# 9xmodule_routed.net
KiCad netlist of a schematic drawn in EAGLE
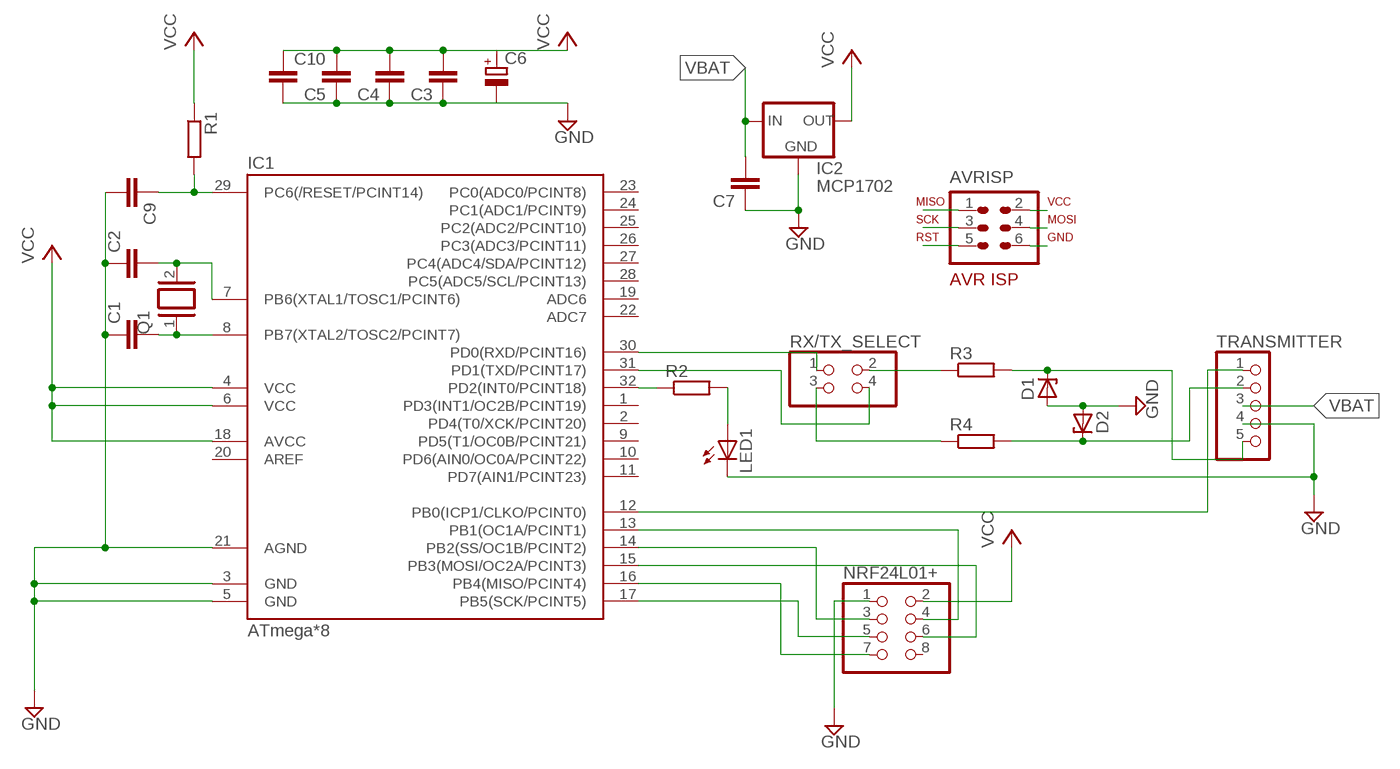
[diagram p0: schematic, sheet 1]

(export (version "E")
  (design (tool "Eeschema 10.0.6"))
  (components
    (comp (ref "AVRISP")
      (value "AVR-ISP-6VERT")
      (footprint "eagle-import:AVR-ISP-6")
      (libsource (lib "eagle-import") (part "AVR-ISP-6VERT"))
    )
    (comp (ref "C1")
      (value "C-EUC0805")
      (footprint "eagle-import:C0805")
      (libsource (lib "eagle-import") (part "C-EUC0805"))
    )
    (comp (ref "C2")
      (value "C-EUC0805")
      (footprint "eagle-import:C0805")
      (libsource (lib "eagle-import") (part "C-EUC0805"))
    )
    (comp (ref "C3")
      (value "C-EUC0805")
      (footprint "eagle-import:C0805")
      (libsource (lib "eagle-import") (part "C-EUC0805"))
    )
    (comp (ref "C4")
      (value "C-EUC0805")
      (footprint "eagle-import:C0805")
      (libsource (lib "eagle-import") (part "C-EUC0805"))
    )
    (comp (ref "C5")
      (value "C-EUC0805")
      (footprint "eagle-import:C0805")
      (libsource (lib "eagle-import") (part "C-EUC0805"))
    )
    (comp (ref "C6")
      (value "CPOL-EUE2.5-6")
      (footprint "eagle-import:E2,5-6")
      (libsource (lib "eagle-import") (part "CPOL-EUE2.5-6"))
    )
    (comp (ref "C7")
      (value "C-EUC0805")
      (footprint "eagle-import:C0805")
      (libsource (lib "eagle-import") (part "C-EUC0805"))
    )
    (comp (ref "C9")
      (value "C-EUC0805")
      (footprint "eagle-import:C0805")
      (libsource (lib "eagle-import") (part "C-EUC0805"))
    )
    (comp (ref "C10")
      (value "C-EUC0805")
      (footprint "eagle-import:C0805")
      (libsource (lib "eagle-import") (part "C-EUC0805"))
    )
    (comp (ref "D1")
      (value "ZENER-DIODESOD80C")
      (footprint "eagle-import:SOD80C")
      (libsource (lib "eagle-import") (part "ZENER-DIODESOD80C"))
    )
    (comp (ref "D2")
      (value "ZENER-DIODESOD80C")
      (footprint "eagle-import:SOD80C")
      (libsource (lib "eagle-import") (part "ZENER-DIODESOD80C"))
    )
    (comp (ref "IC1")
      (value "ATmega*8")
      (footprint "eagle-import:TQFP32-08")
      (libsource (lib "eagle-import") (part "MEGA48/88/168-AU"))
    )
    (comp (ref "IC2")
      (value "MCP1702")
      (footprint "eagle-import:TO-92")
      (libsource (lib "eagle-import") (part "MCP1702"))
    )
    (comp (ref "LED1")
      (value "LEDSMT1206")
      (footprint "eagle-import:1206")
      (libsource (lib "eagle-import") (part "LEDSMT1206"))
    )
    (comp (ref "NRF24L01+")
      (value "PINHD-2X4")
      (footprint "eagle-import:2X04")
      (libsource (lib "eagle-import") (part "PINHD-2X4"))
    )
    (comp (ref "Q1")
      (value "XTAL/S")
      (footprint "eagle-import:QS")
      (libsource (lib "eagle-import") (part "XTAL/S"))
    )
    (comp (ref "R1")
      (value "R-EU_M0805")
      (footprint "eagle-import:M0805")
      (libsource (lib "eagle-import") (part "R-EU_M0805"))
    )
    (comp (ref "R2")
      (value "R-EU_M0805")
      (footprint "eagle-import:M0805")
      (libsource (lib "eagle-import") (part "R-EU_M0805"))
    )
    (comp (ref "R3")
      (value "R-EU_M0805")
      (footprint "eagle-import:M0805")
      (libsource (lib "eagle-import") (part "R-EU_M0805"))
    )
    (comp (ref "R4")
      (value "R-EU_M0805")
      (footprint "eagle-import:M0805")
      (libsource (lib "eagle-import") (part "R-EU_M0805"))
    )
    (comp (ref "RX/TX_SELECT")
      (value "PINHD-2X2")
      (footprint "eagle-import:2X02")
      (libsource (lib "eagle-import") (part "PINHD-2X2"))
    )
    (comp (ref "TRANSMITTER")
      (value "PINHD-1X5")
      (footprint "eagle-import:1X05")
      (libsource (lib "eagle-import") (part "PINHD-1X5"))
    )
  )
  (nets
    (net (code "1") (name "/MISO") (class "Default")
      (node (ref "AVRISP") (pin "1") (pinfunction "1_1") (pintype "passive"))
      (node (ref "IC1") (pin "16") (pinfunction "PB4(MISO/PCINT4)_16") (pintype "bidirectional"))
      (node (ref "NRF24L01+") (pin "7") (pinfunction "7_7") (pintype "passive"))
    )
    (net (code "2") (name "/MOSI") (class "Default")
      (node (ref "AVRISP") (pin "4") (pinfunction "4_4") (pintype "passive"))
      (node (ref "IC1") (pin "15") (pinfunction "PB3(MOSI/OC2A/PCINT3)_15") (pintype "bidirectional"))
      (node (ref "NRF24L01+") (pin "6") (pinfunction "6_6") (pintype "passive"))
    )
    (net (code "3") (name "/RST") (class "Default")
      (node (ref "AVRISP") (pin "5") (pinfunction "5_5") (pintype "passive"))
      (node (ref "C9") (pin "1") (pinfunction "1_1") (pintype "passive"))
      (node (ref "IC1") (pin "29") (pinfunction "PC6(/RESET/PCINT14)_29") (pintype "bidirectional"))
      (node (ref "R1") (pin "2") (pinfunction "2_2") (pintype "passive"))
    )
    (net (code "4") (name "/SCK") (class "Default")
      (node (ref "AVRISP") (pin "3") (pinfunction "3_3") (pintype "passive"))
      (node (ref "IC1") (pin "17") (pinfunction "PB5(SCK/PCINT5)_17") (pintype "bidirectional"))
      (node (ref "NRF24L01+") (pin "5") (pinfunction "5_5") (pintype "passive"))
    )
    (net (code "5") (name "GND") (class "Default")
      (node (ref "AVRISP") (pin "6") (pinfunction "6_6") (pintype "passive"))
      (node (ref "C1") (pin "1") (pinfunction "1_1") (pintype "passive"))
      (node (ref "C10") (pin "2") (pinfunction "2_2") (pintype "passive"))
      (node (ref "C2") (pin "1") (pinfunction "1_1") (pintype "passive"))
      (node (ref "C3") (pin "1") (pinfunction "1_1") (pintype "passive"))
      (node (ref "C4") (pin "1") (pinfunction "1_1") (pintype "passive"))
      (node (ref "C5") (pin "1") (pinfunction "1_1") (pintype "passive"))
      (node (ref "C6") (pin "-") (pinfunction "-_-") (pintype "passive"))
      (node (ref "C7") (pin "1") (pinfunction "1_1") (pintype "passive"))
      (node (ref "C9") (pin "2") (pinfunction "2_2") (pintype "passive"))
      (node (ref "D1") (pin "A") (pinfunction "A_A") (pintype "passive"))
      (node (ref "D2") (pin "A") (pinfunction "A_A") (pintype "passive"))
      (node (ref "IC1") (pin "21") (pinfunction "AGND_21") (pintype "power_in"))
      (node (ref "IC1") (pin "3") (pinfunction "GND_3") (pintype "power_in"))
      (node (ref "IC1") (pin "5") (pinfunction "GND_5") (pintype "power_in"))
      (node (ref "IC2") (pin "1") (pinfunction "GND_1") (pintype "power_in"))
      (node (ref "LED1") (pin "C") (pinfunction "C_C") (pintype "passive"))
      (node (ref "NRF24L01+") (pin "1") (pinfunction "1_1") (pintype "passive"))
      (node (ref "TRANSMITTER") (pin "4") (pinfunction "4_4") (pintype "passive"))
    )
    (net (code "6") (name "Net-(D1-PadC)") (class "Default")
      (node (ref "D1") (pin "C") (pinfunction "C_C") (pintype "passive"))
      (node (ref "R3") (pin "2") (pinfunction "2_2") (pintype "passive"))
      (node (ref "TRANSMITTER") (pin "5") (pinfunction "5_5") (pintype "passive"))
    )
    (net (code "7") (name "Net-(D2-PadC)") (class "Default")
      (node (ref "D2") (pin "C") (pinfunction "C_C") (pintype "passive"))
      (node (ref "R4") (pin "2") (pinfunction "2_2") (pintype "passive"))
      (node (ref "TRANSMITTER") (pin "2") (pinfunction "2_2") (pintype "passive"))
    )
    (net (code "8") (name "Net-(IC1-PB0(ICP1{slash}CLKO{slash}PCINT0))") (class "Default")
      (node (ref "IC1") (pin "12") (pinfunction "PB0(ICP1/CLKO/PCINT0)_12") (pintype "bidirectional"))
      (node (ref "TRANSMITTER") (pin "1") (pinfunction "1_1") (pintype "passive"))
    )
    (net (code "9") (name "Net-(IC1-PB1(OC1A{slash}PCINT1))") (class "Default")
      (node (ref "IC1") (pin "13") (pinfunction "PB1(OC1A/PCINT1)_13") (pintype "bidirectional"))
      (node (ref "NRF24L01+") (pin "4") (pinfunction "4_4") (pintype "passive"))
    )
    (net (code "10") (name "Net-(IC1-PB2(SS{slash}OC1B{slash}PCINT2))") (class "Default")
      (node (ref "IC1") (pin "14") (pinfunction "PB2(SS/OC1B/PCINT2)_14") (pintype "bidirectional"))
      (node (ref "NRF24L01+") (pin "3") (pinfunction "3_3") (pintype "passive"))
    )
    (net (code "11") (name "Net-(IC1-PB6(XTAL1{slash}TOSC1{slash}PCINT6))") (class "Default")
      (node (ref "C2") (pin "2") (pinfunction "2_2") (pintype "passive"))
      (node (ref "IC1") (pin "7") (pinfunction "PB6(XTAL1/TOSC1/PCINT6)_7") (pintype "bidirectional"))
      (node (ref "Q1") (pin "2") (pinfunction "2_2") (pintype "passive"))
    )
    (net (code "12") (name "Net-(IC1-PB7(XTAL2{slash}TOSC2{slash}PCINT7))") (class "Default")
      (node (ref "C1") (pin "2") (pinfunction "2_2") (pintype "passive"))
      (node (ref "IC1") (pin "8") (pinfunction "PB7(XTAL2/TOSC2/PCINT7)_8") (pintype "bidirectional"))
      (node (ref "Q1") (pin "1") (pinfunction "1_1") (pintype "passive"))
    )
    (net (code "13") (name "Net-(IC1-PD0(RXD{slash}PCINT16))") (class "Default")
      (node (ref "IC1") (pin "30") (pinfunction "PD0(RXD/PCINT16)_30") (pintype "bidirectional"))
      (node (ref "RX/TX_SELECT") (pin "1") (pinfunction "1_1") (pintype "passive"))
    )
    (net (code "14") (name "Net-(IC1-PD1(TXD{slash}PCINT17))") (class "Default")
      (node (ref "IC1") (pin "31") (pinfunction "PD1(TXD/PCINT17)_31") (pintype "bidirectional"))
      (node (ref "RX/TX_SELECT") (pin "4") (pinfunction "4_4") (pintype "passive"))
    )
    (net (code "15") (name "Net-(IC1-PD2(INT0{slash}PCINT18))") (class "Default")
      (node (ref "IC1") (pin "32") (pinfunction "PD2(INT0/PCINT18)_32") (pintype "bidirectional"))
      (node (ref "R2") (pin "1") (pinfunction "1_1") (pintype "passive"))
    )
    (net (code "16") (name "Net-(LED1-PadA)") (class "Default")
      (node (ref "LED1") (pin "A") (pinfunction "A_A") (pintype "passive"))
      (node (ref "R2") (pin "2") (pinfunction "2_2") (pintype "passive"))
    )
    (net (code "17") (name "Net-(R3-Pad1)") (class "Default")
      (node (ref "R3") (pin "1") (pinfunction "1_1") (pintype "passive"))
      (node (ref "RX/TX_SELECT") (pin "2") (pinfunction "2_2") (pintype "passive"))
    )
    (net (code "18") (name "Net-(R4-Pad1)") (class "Default")
      (node (ref "R4") (pin "1") (pinfunction "1_1") (pintype "passive"))
      (node (ref "RX/TX_SELECT") (pin "3") (pinfunction "3_3") (pintype "passive"))
    )
    (net (code "19") (name "VBAT") (class "Default")
      (node (ref "C7") (pin "2") (pinfunction "2_2") (pintype "passive"))
      (node (ref "IC2") (pin "2") (pinfunction "IN_2") (pintype "power_in"))
      (node (ref "TRANSMITTER") (pin "3") (pinfunction "3_3") (pintype "passive"))
    )
    (net (code "20") (name "VCC") (class "Default")
      (node (ref "AVRISP") (pin "2") (pinfunction "2_2") (pintype "passive"))
      (node (ref "C10") (pin "1") (pinfunction "1_1") (pintype "passive"))
      (node (ref "C3") (pin "2") (pinfunction "2_2") (pintype "passive"))
      (node (ref "C4") (pin "2") (pinfunction "2_2") (pintype "passive"))
      (node (ref "C5") (pin "2") (pinfunction "2_2") (pintype "passive"))
      (node (ref "C6") (pin "+") (pinfunction "+_+") (pintype "passive"))
      (node (ref "IC1") (pin "18") (pinfunction "AVCC_18") (pintype "passive"))
      (node (ref "IC1") (pin "4") (pinfunction "VCC_4") (pintype "power_in"))
      (node (ref "IC1") (pin "6") (pinfunction "VCC_6") (pintype "power_in"))
      (node (ref "IC2") (pin "3") (pinfunction "OUT_3") (pintype "power_in"))
      (node (ref "NRF24L01+") (pin "2") (pinfunction "2_2") (pintype "passive"))
      (node (ref "R1") (pin "1") (pinfunction "1_1") (pintype "passive"))
    )
    (net (code "21") (name "unconnected-(IC1-ADC6-Pad19)") (class "Default")
      (node (ref "IC1") (pin "19") (pinfunction "ADC6_19") (pintype "passive"))
    )
    (net (code "22") (name "unconnected-(IC1-ADC7-Pad22)") (class "Default")
      (node (ref "IC1") (pin "22") (pinfunction "ADC7_22") (pintype "passive"))
    )
    (net (code "23") (name "unconnected-(IC1-AREF-Pad20)") (class "Default")
      (node (ref "IC1") (pin "20") (pinfunction "AREF_20") (pintype "passive"))
    )
    (net (code "24") (name "unconnected-(IC1-PC0(ADC0{slash}PCINT8)-Pad23)") (class "Default")
      (node (ref "IC1") (pin "23") (pinfunction "PC0(ADC0/PCINT8)_23") (pintype "bidirectional"))
    )
    (net (code "25") (name "unconnected-(IC1-PC1(ADC1{slash}PCINT9)-Pad24)") (class "Default")
      (node (ref "IC1") (pin "24") (pinfunction "PC1(ADC1/PCINT9)_24") (pintype "bidirectional"))
    )
    (net (code "26") (name "unconnected-(IC1-PC2(ADC2{slash}PCINT10)-Pad25)") (class "Default")
      (node (ref "IC1") (pin "25") (pinfunction "PC2(ADC2/PCINT10)_25") (pintype "bidirectional"))
    )
    (net (code "27") (name "unconnected-(IC1-PC3(ADC3{slash}PCINT11)-Pad26)") (class "Default")
      (node (ref "IC1") (pin "26") (pinfunction "PC3(ADC3/PCINT11)_26") (pintype "bidirectional"))
    )
    (net (code "28") (name "unconnected-(IC1-PC4(ADC4{slash}SDA{slash}PCINT12)-Pad27)") (class "Default")
      (node (ref "IC1") (pin "27") (pinfunction "PC4(ADC4/SDA/PCINT12)_27") (pintype "bidirectional"))
    )
    (net (code "29") (name "unconnected-(IC1-PC5(ADC5{slash}SCL{slash}PCINT13)-Pad28)") (class "Default")
      (node (ref "IC1") (pin "28") (pinfunction "PC5(ADC5/SCL/PCINT13)_28") (pintype "bidirectional"))
    )
    (net (code "30") (name "unconnected-(IC1-PD3(INT1{slash}OC2B{slash}PCINT19)-Pad1)") (class "Default")
      (node (ref "IC1") (pin "1") (pinfunction "PD3(INT1/OC2B/PCINT19)_1") (pintype "bidirectional"))
    )
    (net (code "31") (name "unconnected-(IC1-PD4(T0{slash}XCK{slash}PCINT20)-Pad2)") (class "Default")
      (node (ref "IC1") (pin "2") (pinfunction "PD4(T0/XCK/PCINT20)_2") (pintype "bidirectional"))
    )
    (net (code "32") (name "unconnected-(IC1-PD5(T1{slash}OC0B{slash}PCINT21)-Pad9)") (class "Default")
      (node (ref "IC1") (pin "9") (pinfunction "PD5(T1/OC0B/PCINT21)_9") (pintype "bidirectional"))
    )
    (net (code "33") (name "unconnected-(IC1-PD6(AIN0{slash}OC0A{slash}PCINT22)-Pad10)") (class "Default")
      (node (ref "IC1") (pin "10") (pinfunction "PD6(AIN0/OC0A/PCINT22)_10") (pintype "bidirectional"))
    )
    (net (code "34") (name "unconnected-(IC1-PD7(AIN1{slash}PCINT23)-Pad11)") (class "Default")
      (node (ref "IC1") (pin "11") (pinfunction "PD7(AIN1/PCINT23)_11") (pintype "bidirectional"))
    )
    (net (code "35") (name "unconnected-(NRF24L01+-Pad8)") (class "Default")
      (node (ref "NRF24L01+") (pin "8") (pinfunction "8_8") (pintype "passive"))
    )
  )
)
